# 05_-_POWER.net
KiCad netlist of a schematic drawn in Altium Designer
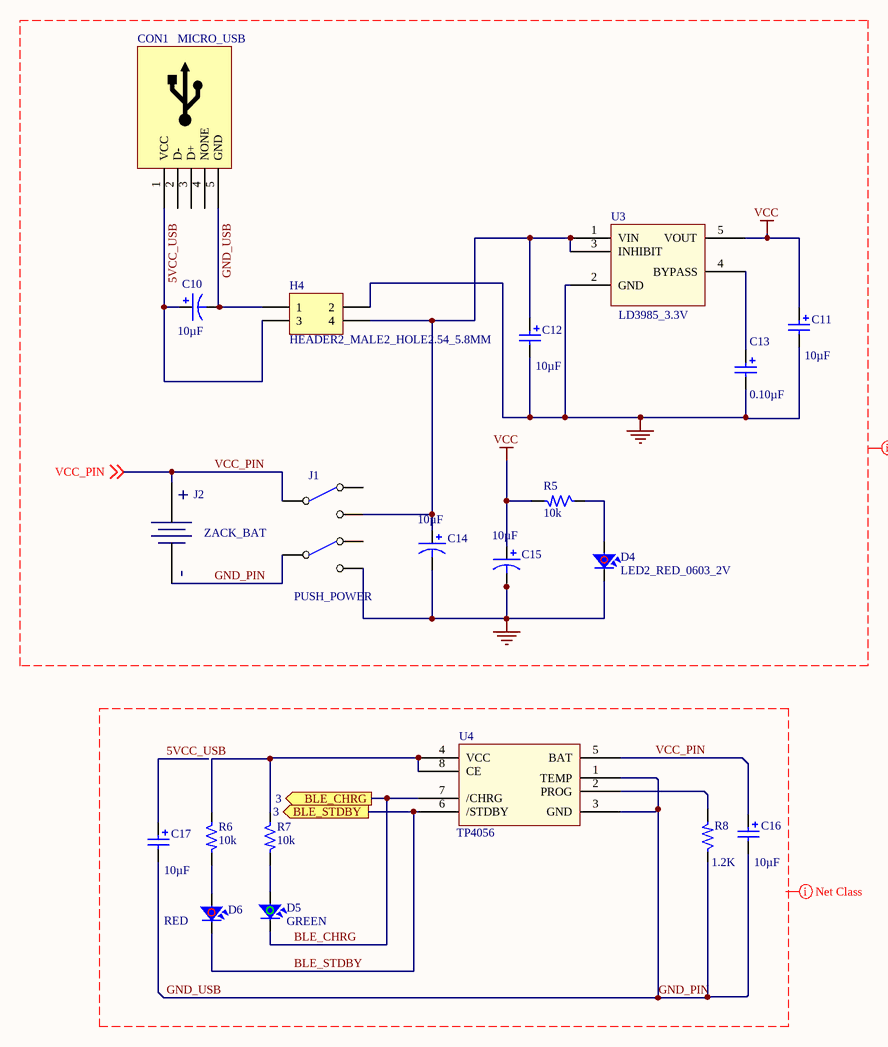
[diagram p0: [05] - POWER.SchDoc]

(export (version "E")
  (design (tool "Eeschema 10.0.6"))
  (components
    (comp (ref "C10")
      (value "C_106_0805_TANTALUM_16V")
      (footprint "CAP_SMD0805 - TANTALUM")
      (description "CAP TANT 10UF 16V 10% 0805")
      (fields
        (field (name "MANUFACTURER") "AVX Corporation")
        (field (name "MANUFACTURER PART NUMBER") "TPCR106K016R1800")
        (field (name "CAPACITANCE") "10µF")
      )
      (libsource (lib "ALTIUM_LIB") (part "C_106_0805_TANTALUM_16V"))
    )
    (comp (ref "C11")
      (value "C_106_0805_CERAMIC_16V")
      (footprint "CAP_SMD0805")
      (description "CAP CER 10UF 16V X5R 0805")
      (fields
        (field (name "MANUFACTURER") "Murata Electronics North America")
        (field (name "MANUFACTURER PART NUMBER") "GRM21BR61C106KE15K")
        (field (name "CAPACITANCE") "10µF")
      )
      (libsource (lib "ALTIUM_LIB") (part "C_106_0805_CERAMIC_16V"))
    )
    (comp (ref "C12")
      (value "C_106_0805_CERAMIC_16V")
      (footprint "CAP_SMD0805")
      (description "CAP CER 10UF 16V X5R 0805")
      (fields
        (field (name "MANUFACTURER") "Murata Electronics North America")
        (field (name "MANUFACTURER PART NUMBER") "GRM21BR61C106KE15K")
        (field (name "CAPACITANCE") "10µF")
      )
      (libsource (lib "ALTIUM_LIB") (part "C_106_0805_CERAMIC_16V"))
    )
    (comp (ref "C13")
      (value "C_104_0603_CERAMIC_16V")
      (footprint "CAP_SMD0603")
      (description "CAP CER 0.1UF 16V X7R 0603")
      (fields
        (field (name "MANUFACTURER") "Murata Electronics North America")
        (field (name "MANUFACTURER PART NUMBER") "GRM188R71C104KA01D")
        (field (name "CAPACITANCE") "0.10µF")
      )
      (libsource (lib "ALTIUM_LIB") (part "C_104_0603_CERAMIC_16V"))
    )
    (comp (ref "C14")
      (value "C_106_1206_TANTALUM_25V")
      (footprint "CAP_SMD1206_TANTALUM")
      (description "CAP TANT 10UF 25V 10% 1206")
      (fields
        (field (name "MANUFACTURER") "AVX Corporation")
        (field (name "MANUFACTURER PART NUMBER") "F951E106KAAAQ2")
        (field (name "CAPACITANCE") "10µF")
      )
      (libsource (lib "ALTIUM_LIB") (part "C_106_1206_TANTALUM_25V"))
    )
    (comp (ref "C15")
      (value "C_106_1206_TANTALUM_25V")
      (footprint "CAP_SMD1206_TANTALUM")
      (description "CAP TANT 10UF 25V 10% 1206")
      (fields
        (field (name "MANUFACTURER") "AVX Corporation")
        (field (name "MANUFACTURER PART NUMBER") "F951E106KAAAQ2")
        (field (name "CAPACITANCE") "10µF")
      )
      (libsource (lib "ALTIUM_LIB") (part "C_106_1206_TANTALUM_25V"))
    )
    (comp (ref "C16")
      (value "C_106_0805_CERAMIC_16V")
      (footprint "CAP_SMD0805")
      (description "CAP CER 10UF 16V X5R 0805")
      (fields
        (field (name "MANUFACTURER") "Murata Electronics North America")
        (field (name "MANUFACTURER PART NUMBER") "GRM21BR61C106KE15K")
        (field (name "CAPACITANCE") "10µF")
      )
      (libsource (lib "ALTIUM_LIB") (part "C_106_0805_CERAMIC_16V"))
    )
    (comp (ref "C17")
      (value "C_106_0805_CERAMIC_16V")
      (footprint "CAP_SMD0805")
      (description "CAP CER 10UF 16V X5R 0805")
      (fields
        (field (name "MANUFACTURER") "Murata Electronics North America")
        (field (name "MANUFACTURER PART NUMBER") "GRM21BR61C106KE15K")
        (field (name "CAPACITANCE") "10µF")
      )
      (libsource (lib "ALTIUM_LIB") (part "C_106_0805_CERAMIC_16V"))
    )
    (comp (ref "CON1")
      (value "MICRO_USB")
      (footprint "CON_MICRO_USB_HOLE")
      (description "CONN RCPT STD MICRO USB TYPE B")
      (fields
        (field (name "MANUFACTURER") "Amphenol FCI")
        (field (name "MANUFACTURER PART NUMBER") "10103593-0001LF")
      )
      (libsource (lib "ALTIUM_LIB") (part "CONNECT_MICRO_USB_SURFACE"))
    )
    (comp (ref "D4")
      (value "LED2_RED_0603_2V")
      (footprint "LED_RED_SMD0603")
      (description "LED RED CLEAR 0603 SMD")
      (fields
        (field (name "MANUFACTURER") "Lite-On Inc.")
        (field (name "MANUFACTURER PART NUMBER") "LTST-C191KRKT")
      )
      (libsource (lib "ALTIUM_LIB") (part "LED2_RED_0603_2V"))
    )
    (comp (ref "D5")
      (value "GREEN")
      (footprint "LED_GREEN_SMD0603")
      (description "LED GREEN CLEAR 0603 SMD")
      (fields
        (field (name "MANUFACTURER") "Lite-On Inc.")
        (field (name "MANUFACTURER PART NUMBER") "LTST-C191KGKT")
      )
      (libsource (lib "ALTIUM_LIB") (part "LED2_GREEN_0603_2V"))
    )
    (comp (ref "D6")
      (value "RED")
      (footprint "LED_RED_SMD0603")
      (description "LED RED CLEAR 0603 SMD")
      (fields
        (field (name "MANUFACTURER") "Lite-On Inc.")
        (field (name "MANUFACTURER PART NUMBER") "LTST-C191KRKT")
      )
      (libsource (lib "ALTIUM_LIB") (part "LED2_RED_0603_2V"))
    )
    (comp (ref "H4")
      (value "HEADER2_MALE2_HOLE2.54_5.8MM")
      (footprint "HEADER2_MALE2_HOLE2.54")
      (description "02+02 DIL VERT PIN HDR")
      (fields
        (field (name "MANUFACTURER") "Harwin Inc.")
        (field (name "MANUFACTURER PART NUMBER") "M20-9760246")
      )
      (libsource (lib "ALTIUM_LIB") (part "HEADER2_MALE2_HOLE2.54_5.8MM"))
    )
    (comp (ref "J1")
      (value "PUSH_POWER")
      (footprint "SW6_DPDT_POWER")
      (description "SWITCH PUSH DPDT 0.1A 30V")
      (fields (field (name "MANUFACTURER") "Apem Inc.") (field (name "MANUFACTURER PART NUMBER") "MHPS2266"))
      (libsource (lib "ALTIUM_LIB") (part "SW6_DPDT_HOLE_PUSH_0.1A_30A"))
    )
    (comp (ref "J2")
      (value "ZACK_BAT")
      (footprint "ZACK_BAT")
      (description "CONN HEADER VERT 2POS .100 TIN")
      (fields
        (field (name "MANUFACTURER") "TE Connectivity AMP Connectors")
        (field (name "MANUFACTURER PART NUMBER") "640456-2")
      )
      (libsource (lib "ALTIUM_LIB") (part "ZACK2_HOLE_BATTERY_LOCK"))
    )
    (comp (ref "R5")
      (value "R_10K_SMD0603_1%_1/10W")
      (footprint "RES_SMD0603")
      (description "RES SMD 10K OHM 1% 1/10W 0603")
      (fields
        (field (name "MANUFACTURER") "Yageo")
        (field (name "MANUFACTURER PART NUMBER") "RC0603FR-0710KL")
        (field (name "RESISTANCE (OHMS)") "10k")
      )
      (libsource (lib "ALTIUM_LIB") (part "R_10K_SMD0603_1%_1/10W"))
    )
    (comp (ref "R6")
      (value "R_10K_SMD0603_1%_1/10W")
      (footprint "RES_SMD0603")
      (description "RES SMD 10K OHM 1% 1/10W 0603")
      (fields
        (field (name "MANUFACTURER") "Yageo")
        (field (name "MANUFACTURER PART NUMBER") "RC0603FR-0710KL")
        (field (name "RESISTANCE (OHMS)") "10k")
      )
      (libsource (lib "ALTIUM_LIB") (part "R_10K_SMD0603_1%_1/10W"))
    )
    (comp (ref "R7")
      (value "R_10K_SMD0603_1%_1/10W")
      (footprint "RES_SMD0603")
      (description "RES SMD 10K OHM 1% 1/10W 0603")
      (fields
        (field (name "MANUFACTURER") "Yageo")
        (field (name "MANUFACTURER PART NUMBER") "RC0603FR-0710KL")
        (field (name "RESISTANCE (OHMS)") "10k")
      )
      (libsource (lib "ALTIUM_LIB") (part "R_10K_SMD0603_1%_1/10W"))
    )
    (comp (ref "R8")
      (value "R_1K2_SMD0603_1%_1/10W")
      (footprint "RES_SMD0603")
      (description "RES SMD 1.2K OHM 1% 1/10W 0603")
      (fields
        (field (name "MANUFACTURER") "Yageo")
        (field (name "MANUFACTURER PART NUMBER") "RC0603FR-071K2L")
        (field (name "RESISTANCE (OHMS)") "1.2K")
      )
      (libsource (lib "ALTIUM_LIB") (part "R_1K2_SMD0603_1%_1/10W"))
    )
    (comp (ref "U3")
      (value "LD3985_3.3V")
      (footprint "POWER_LDO_LDR3985-3.3")
      (description "IC REG LDO 3.3V 0.15A SOT23-5")
      (fields
        (field (name "MANUFACTURER") "STMicroelectronics")
        (field (name "MANUFACTURER PART NUMBER") "LD3985M33R")
      )
      (libsource (lib "ALTIUM_LIB") (part "POWER_LDO_LD3985_3.3V_SOT-23-5"))
    )
    (comp (ref "U4")
      (value "TP4056")
      (footprint "POWER__CHARGE_TP4056")
      (description "IC CHARGR BATTERY L-ION  SOP8")
      (fields (field (name "MANUFACTURER") "NanJing"))
      (libsource (lib "ALTIUM_LIB") (part "POWER_CHARGE_TP4056_4.2V_SOP8"))
    )
  )
  (nets
    (net (code "1") (name "/5VCC_USB") (class "Default")
      (node (ref "C10") (pin "1") (pinfunction "1_1") (pintype "passive"))
      (node (ref "C17") (pin "1") (pinfunction "1_1") (pintype "passive"))
      (node (ref "CON1") (pin "1") (pinfunction "VCC_1") (pintype "passive"))
      (node (ref "H4") (pin "3") (pinfunction "3_3") (pintype "passive"))
    )
    (net (code "2") (name "/BLE_CHRG") (class "Default")
      (node (ref "D5") (pin "2") (pinfunction "2_2") (pintype "passive"))
      (node (ref "U4") (pin "7") (pinfunction "/CHRG_7") (pintype "passive"))
    )
    (net (code "3") (name "/BLE_STDBY") (class "Default")
      (node (ref "D6") (pin "2") (pinfunction "2_2") (pintype "passive"))
      (node (ref "U4") (pin "6") (pinfunction "/STDBY_6") (pintype "passive"))
    )
    (net (code "4") (name "/GND_PIN") (class "Default")
      (node (ref "C10") (pin "2") (pinfunction "2_2") (pintype "passive"))
      (node (ref "C16") (pin "2") (pinfunction "2_2") (pintype "passive"))
      (node (ref "C17") (pin "2") (pinfunction "2_2") (pintype "passive"))
      (node (ref "CON1") (pin "5") (pinfunction "GND_5") (pintype "passive"))
      (node (ref "H4") (pin "1") (pinfunction "1_1") (pintype "passive"))
      (node (ref "J1") (pin "5") (pinfunction "COMMON_5") (pintype "passive"))
      (node (ref "J2") (pin "2") (pinfunction "-_2") (pintype "passive"))
      (node (ref "R8") (pin "1") (pinfunction "1_1") (pintype "passive"))
      (node (ref "U4") (pin "1") (pinfunction "TEMP_1") (pintype "passive"))
      (node (ref "U4") (pin "3") (pinfunction "GND_3") (pintype "passive"))
    )
    (net (code "5") (name "GND") (class "Default")
      (node (ref "C11") (pin "2") (pinfunction "2_2") (pintype "passive"))
      (node (ref "C12") (pin "2") (pinfunction "2_2") (pintype "passive"))
      (node (ref "C13") (pin "2") (pinfunction "2_2") (pintype "passive"))
      (node (ref "C14") (pin "2") (pinfunction "2_2") (pintype "passive"))
      (node (ref "C15") (pin "2") (pinfunction "2_2") (pintype "passive"))
      (node (ref "D4") (pin "2") (pinfunction "2_2") (pintype "passive"))
      (node (ref "H4") (pin "2") (pinfunction "2_2") (pintype "passive"))
      (node (ref "J1") (pin "4") (pinfunction "NO_4") (pintype "passive"))
      (node (ref "U3") (pin "2") (pinfunction "GND_2") (pintype "passive"))
    )
    (net (code "6") (name "Net-(D4-Pad1)") (class "Default")
      (node (ref "D4") (pin "1") (pinfunction "1_1") (pintype "passive"))
      (node (ref "R5") (pin "1") (pinfunction "1_1") (pintype "passive"))
    )
    (net (code "7") (name "Net-(D5-Pad1)") (class "Default")
      (node (ref "D5") (pin "1") (pinfunction "1_1") (pintype "passive"))
      (node (ref "R7") (pin "2") (pinfunction "2_2") (pintype "passive"))
    )
    (net (code "8") (name "Net-(D6-Pad1)") (class "Default")
      (node (ref "D6") (pin "1") (pinfunction "1_1") (pintype "passive"))
      (node (ref "R6") (pin "2") (pinfunction "2_2") (pintype "passive"))
    )
    (net (code "9") (name "Net-(U3-BYPASS)") (class "Default")
      (node (ref "C13") (pin "1") (pinfunction "1_1") (pintype "passive"))
      (node (ref "U3") (pin "4") (pinfunction "BYPASS_4") (pintype "passive"))
    )
    (net (code "10") (name "Net-(U3-INHIBIT)") (class "Default")
      (node (ref "C12") (pin "1") (pinfunction "1_1") (pintype "passive"))
      (node (ref "C14") (pin "1") (pinfunction "1_1") (pintype "passive"))
      (node (ref "H4") (pin "4") (pinfunction "4_4") (pintype "passive"))
      (node (ref "J1") (pin "3") (pinfunction "NO_3") (pintype "passive"))
      (node (ref "U3") (pin "1") (pinfunction "VIN_1") (pintype "passive"))
      (node (ref "U3") (pin "3") (pinfunction "INHIBIT_3") (pintype "passive"))
    )
    (net (code "11") (name "Net-(U4-CE)") (class "Default")
      (node (ref "R6") (pin "1") (pinfunction "1_1") (pintype "passive"))
      (node (ref "R7") (pin "1") (pinfunction "1_1") (pintype "passive"))
      (node (ref "U4") (pin "4") (pinfunction "VCC_4") (pintype "passive"))
      (node (ref "U4") (pin "8") (pinfunction "CE_8") (pintype "passive"))
    )
    (net (code "12") (name "Net-(U4-PROG)") (class "Default")
      (node (ref "R8") (pin "2") (pinfunction "2_2") (pintype "passive"))
      (node (ref "U4") (pin "2") (pinfunction "PROG_2") (pintype "passive"))
    )
    (net (code "13") (name "VCC") (class "Default")
      (node (ref "C11") (pin "1") (pinfunction "1_1") (pintype "passive"))
      (node (ref "C15") (pin "1") (pinfunction "1_1") (pintype "passive"))
      (node (ref "R5") (pin "2") (pinfunction "2_2") (pintype "passive"))
      (node (ref "U3") (pin "5") (pinfunction "VOUT_5") (pintype "passive"))
    )
    (net (code "14") (name "VCC_PIN") (class "Default")
      (node (ref "C16") (pin "1") (pinfunction "1_1") (pintype "passive"))
      (node (ref "J1") (pin "2") (pinfunction "COMMON_2") (pintype "passive"))
      (node (ref "J2") (pin "1") (pinfunction "+_1") (pintype "passive"))
      (node (ref "U4") (pin "5") (pinfunction "BAT_5") (pintype "passive"))
    )
    (net (code "15") (name "unconnected-(CON1-D+-Pad3)") (class "Default")
      (node (ref "CON1") (pin "3") (pinfunction "D+_3") (pintype "passive"))
    )
    (net (code "16") (name "unconnected-(CON1-D--Pad2)") (class "Default")
      (node (ref "CON1") (pin "2") (pinfunction "D-_2") (pintype "passive"))
    )
    (net (code "17") (name "unconnected-(CON1-NONE-Pad4)") (class "Default")
      (node (ref "CON1") (pin "4") (pinfunction "NONE_4") (pintype "passive"))
    )
    (net (code "18") (name "unconnected-(J1-NC-Pad1)") (class "Default")
      (node (ref "J1") (pin "1") (pinfunction "NC_1") (pintype "passive"))
    )
    (net (code "19") (name "unconnected-(J1-NC-Pad6)") (class "Default")
      (node (ref "J1") (pin "6") (pinfunction "NC_6") (pintype "passive"))
    )
  )
)
